# v3-landshark-handheld-controller.net
KiCad netlist of a schematic drawn in EAGLE
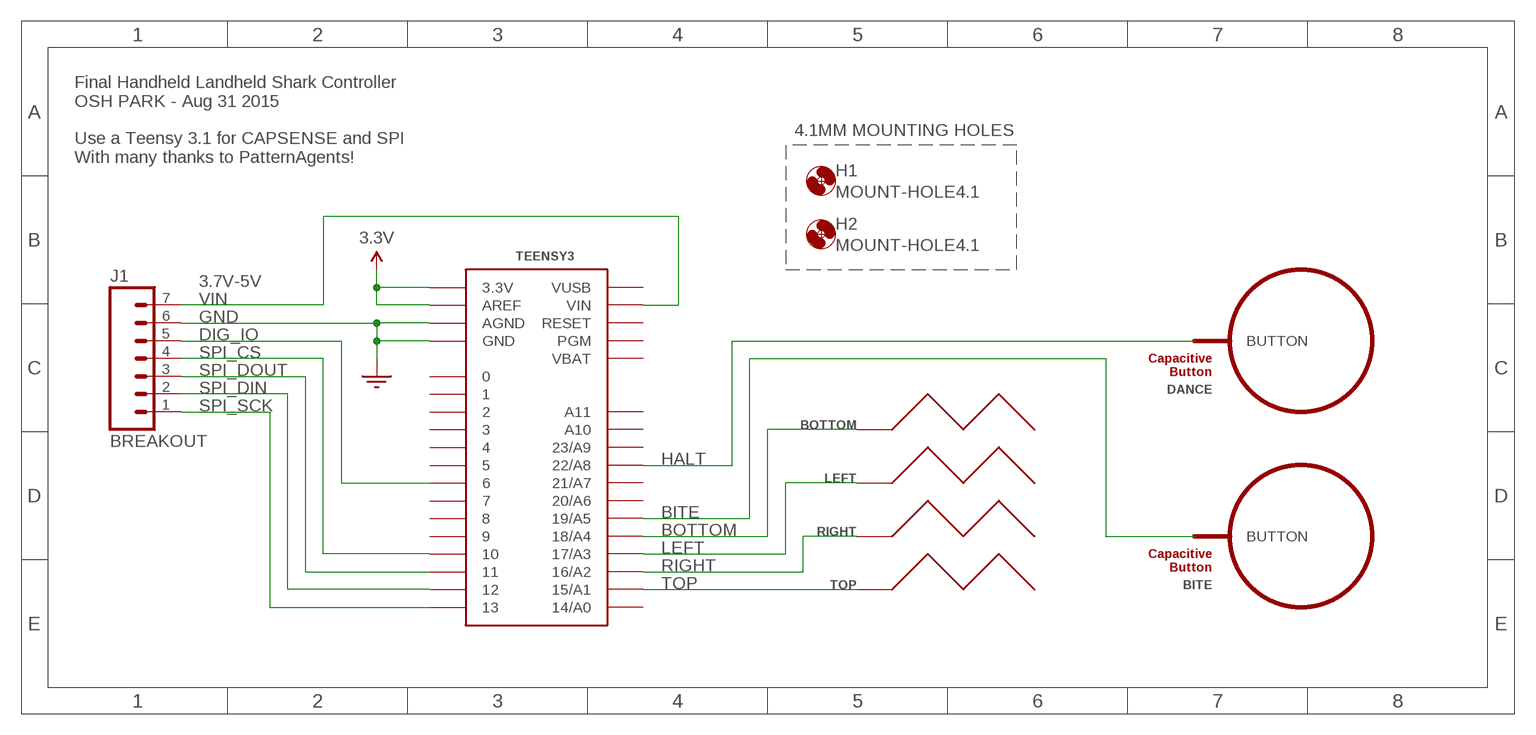
[diagram p0: schematic, sheet 1]

(export (version "E")
  (design (tool "Eeschema 10.0.6"))
  (components
    (comp (ref "BITE")
      (value "BUTTON_PASSIVE_12MM_BITE")
      (footprint "eagle-import:BUTTON_PASSIVE_12MM_BITE")
      (libsource (lib "eagle-import") (part "BUTTON_PASSIVE_12MM_BITE"))
    )
    (comp (ref "BOTTOM")
      (value "SLIDER_PASSIVE_1SEG")
      (footprint "eagle-import:SLIDER_PASSIVE_1SEG_12MM")
      (libsource (lib "eagle-import") (part "SLIDER_PASSIVE_1SEG"))
    )
    (comp (ref "DANCE")
      (value "BUTTON_PASSIVE_12MM_DANCE")
      (footprint "eagle-import:BUTTON_PASSIVE_12MM_DANCE")
      (libsource (lib "eagle-import") (part "BUTTON_PASSIVE_12MM_DANCE"))
    )
    (comp (ref "H1")
      (value "MOUNT-HOLE4.1")
      (footprint "eagle-import:4,1")
      (libsource (lib "eagle-import") (part "MOUNT-HOLE4.1"))
    )
    (comp (ref "H2")
      (value "MOUNT-HOLE4.1")
      (footprint "eagle-import:4,1")
      (libsource (lib "eagle-import") (part "MOUNT-HOLE4.1"))
    )
    (comp (ref "J1")
      (value "BREAKOUT")
      (footprint "eagle-import:1X07_LOCK_LONGPADS")
      (libsource (lib "eagle-import") (part "M07LOCK_LONGPADS"))
    )
    (comp (ref "LEFT")
      (value "SLIDER_PASSIVE_1SEG")
      (footprint "eagle-import:SLIDER_PASSIVE_1SEG_12MM")
      (libsource (lib "eagle-import") (part "SLIDER_PASSIVE_1SEG"))
    )
    (comp (ref "RIGHT")
      (value "SLIDER_PASSIVE_1SEG")
      (footprint "eagle-import:SLIDER_PASSIVE_1SEG_12MM")
      (libsource (lib "eagle-import") (part "SLIDER_PASSIVE_1SEG"))
    )
    (comp (ref "TEENSY3")
      (value "TEENSY_3.0+4")
      (footprint "eagle-import:TEENSY_3.0+4")
      (libsource (lib "eagle-import") (part "TEENSY_3.0+4"))
    )
    (comp (ref "TOP")
      (value "SLIDER_PASSIVE_1SEG")
      (footprint "eagle-import:SLIDER_PASSIVE_1SEG_12MM")
      (libsource (lib "eagle-import") (part "SLIDER_PASSIVE_1SEG"))
    )
  )
  (nets
    (net (code "1") (name "/BITE") (class "Default")
      (node (ref "BITE") (pin "BUTTON") (pinfunction "BUTTON_BUTTON") (pintype "passive"))
      (node (ref "TEENSY3") (pin "19/A5") (pinfunction "19/A5_19/A5") (pintype "bidirectional"))
    )
    (net (code "2") (name "/BOTTOM") (class "Default")
      (node (ref "BOTTOM") (pin "P$1") (pinfunction "SL1_P$1") (pintype "passive"))
      (node (ref "TEENSY3") (pin "18/A4") (pinfunction "18/A4_18/A4") (pintype "bidirectional"))
    )
    (net (code "3") (name "/DIG_IO") (class "Default")
      (node (ref "J1") (pin "5") (pinfunction "5_5") (pintype "passive"))
      (node (ref "TEENSY3") (pin "6") (pinfunction "6_6") (pintype "bidirectional"))
    )
    (net (code "4") (name "/HALT") (class "Default")
      (node (ref "DANCE") (pin "BUTTON") (pinfunction "BUTTON_BUTTON") (pintype "passive"))
      (node (ref "TEENSY3") (pin "22/A8") (pinfunction "22/A8_22/A8") (pintype "bidirectional"))
    )
    (net (code "5") (name "/LEFT") (class "Default")
      (node (ref "LEFT") (pin "P$1") (pinfunction "SL1_P$1") (pintype "passive"))
      (node (ref "TEENSY3") (pin "17/A3") (pinfunction "17/A3_17/A3") (pintype "bidirectional"))
    )
    (net (code "6") (name "/RIGHT") (class "Default")
      (node (ref "RIGHT") (pin "P$1") (pinfunction "SL1_P$1") (pintype "passive"))
      (node (ref "TEENSY3") (pin "16/A2") (pinfunction "16/A2_16/A2") (pintype "bidirectional"))
    )
    (net (code "7") (name "/SPI_CS") (class "Default")
      (node (ref "J1") (pin "4") (pinfunction "4_4") (pintype "passive"))
      (node (ref "TEENSY3") (pin "10") (pinfunction "10_10") (pintype "bidirectional"))
    )
    (net (code "8") (name "/SPI_DIN") (class "Default")
      (node (ref "J1") (pin "2") (pinfunction "2_2") (pintype "passive"))
      (node (ref "TEENSY3") (pin "12") (pinfunction "12_12") (pintype "bidirectional"))
    )
    (net (code "9") (name "/SPI_DOUT") (class "Default")
      (node (ref "J1") (pin "3") (pinfunction "3_3") (pintype "passive"))
      (node (ref "TEENSY3") (pin "11") (pinfunction "11_11") (pintype "bidirectional"))
    )
    (net (code "10") (name "/SPI_SCK") (class "Default")
      (node (ref "J1") (pin "1") (pinfunction "1_1") (pintype "passive"))
      (node (ref "TEENSY3") (pin "13") (pinfunction "13_13") (pintype "bidirectional"))
    )
    (net (code "11") (name "/TOP") (class "Default")
      (node (ref "TEENSY3") (pin "15/A1") (pinfunction "15/A1_15/A1") (pintype "bidirectional"))
      (node (ref "TOP") (pin "P$1") (pinfunction "SL1_P$1") (pintype "passive"))
    )
    (net (code "12") (name "/VBAT") (class "Default")
      (node (ref "TEENSY3") (pin "VBAT") (pinfunction "VBAT_VBAT") (pintype "power_in"))
    )
    (net (code "13") (name "/VIN") (class "Default")
      (node (ref "J1") (pin "7") (pinfunction "7_7") (pintype "passive"))
      (node (ref "TEENSY3") (pin "VIN") (pinfunction "VIN_VIN") (pintype "power_in"))
    )
    (net (code "14") (name "/VUSB") (class "Default")
      (node (ref "TEENSY3") (pin "VUSB") (pinfunction "VUSB_VUSB") (pintype "power_in"))
    )
    (net (code "15") (name "3.3V") (class "Default")
      (node (ref "TEENSY3") (pin "3.3V") (pinfunction "3.3V_3.3V") (pintype "power_in"))
      (node (ref "TEENSY3") (pin "3.3V1") (pinfunction "3.3V_3.3V1") (pintype "power_in"))
      (node (ref "TEENSY3") (pin "AREF") (pinfunction "AREF_AREF") (pintype "power_in"))
    )
    (net (code "16") (name "GND") (class "Default")
      (node (ref "J1") (pin "6") (pinfunction "6_6") (pintype "passive"))
      (node (ref "TEENSY3") (pin "AGND") (pinfunction "AGND_AGND") (pintype "power_in"))
      (node (ref "TEENSY3") (pin "GND") (pinfunction "GND_GND") (pintype "power_in"))
      (node (ref "TEENSY3") (pin "GND1") (pinfunction "GND_GND1") (pintype "power_in"))
    )
    (net (code "17") (name "unconnected-(TEENSY3-Pad0)") (class "Default")
      (node (ref "TEENSY3") (pin "0") (pinfunction "0_0") (pintype "bidirectional"))
    )
    (net (code "18") (name "unconnected-(TEENSY3-Pad1)") (class "Default")
      (node (ref "TEENSY3") (pin "1") (pinfunction "1_1") (pintype "bidirectional"))
    )
    (net (code "19") (name "unconnected-(TEENSY3-Pad2)") (class "Default")
      (node (ref "TEENSY3") (pin "2") (pinfunction "2_2") (pintype "bidirectional"))
    )
    (net (code "20") (name "unconnected-(TEENSY3-Pad3)") (class "Default")
      (node (ref "TEENSY3") (pin "3") (pinfunction "3_3") (pintype "bidirectional"))
    )
    (net (code "21") (name "unconnected-(TEENSY3-Pad4)") (class "Default")
      (node (ref "TEENSY3") (pin "4") (pinfunction "4_4") (pintype "bidirectional"))
    )
    (net (code "22") (name "unconnected-(TEENSY3-Pad5)") (class "Default")
      (node (ref "TEENSY3") (pin "5") (pinfunction "5_5") (pintype "bidirectional"))
    )
    (net (code "23") (name "unconnected-(TEENSY3-Pad7)") (class "Default")
      (node (ref "TEENSY3") (pin "7") (pinfunction "7_7") (pintype "bidirectional"))
    )
    (net (code "24") (name "unconnected-(TEENSY3-Pad8)") (class "Default")
      (node (ref "TEENSY3") (pin "8") (pinfunction "8_8") (pintype "bidirectional"))
    )
    (net (code "25") (name "unconnected-(TEENSY3-Pad9)") (class "Default")
      (node (ref "TEENSY3") (pin "9") (pinfunction "9_9") (pintype "bidirectional"))
    )
    (net (code "26") (name "unconnected-(TEENSY3-Pad14{slash}A0)") (class "Default")
      (node (ref "TEENSY3") (pin "14/A0") (pinfunction "14/A0_14/A0") (pintype "bidirectional"))
    )
    (net (code "27") (name "unconnected-(TEENSY3-Pad20{slash}A6)") (class "Default")
      (node (ref "TEENSY3") (pin "20/A6") (pinfunction "20/A6_20/A6") (pintype "bidirectional"))
    )
    (net (code "28") (name "unconnected-(TEENSY3-Pad21{slash}A7)") (class "Default")
      (node (ref "TEENSY3") (pin "21/A7") (pinfunction "21/A7_21/A7") (pintype "bidirectional"))
    )
    (net (code "29") (name "unconnected-(TEENSY3-Pad23{slash}A9)") (class "Default")
      (node (ref "TEENSY3") (pin "23/A9") (pinfunction "23/A9_23/A9") (pintype "bidirectional"))
    )
    (net (code "30") (name "unconnected-(TEENSY3-PadA10)") (class "Default")
      (node (ref "TEENSY3") (pin "A10") (pinfunction "A10_A10") (pintype "bidirectional"))
    )
    (net (code "31") (name "unconnected-(TEENSY3-PadA11)") (class "Default")
      (node (ref "TEENSY3") (pin "A11") (pinfunction "A11_A11") (pintype "bidirectional"))
    )
    (net (code "32") (name "unconnected-(TEENSY3-PadPGM)") (class "Default")
      (node (ref "TEENSY3") (pin "PGM") (pinfunction "PGM_PGM") (pintype "bidirectional"))
    )
    (net (code "33") (name "unconnected-(TEENSY3-PadRESET)") (class "Default")
      (node (ref "TEENSY3") (pin "RESET") (pinfunction "RESET_RESET") (pintype "bidirectional"))
    )
  )
)
